# er9x.net
KiCad netlist of a schematic drawn in Altium Designer
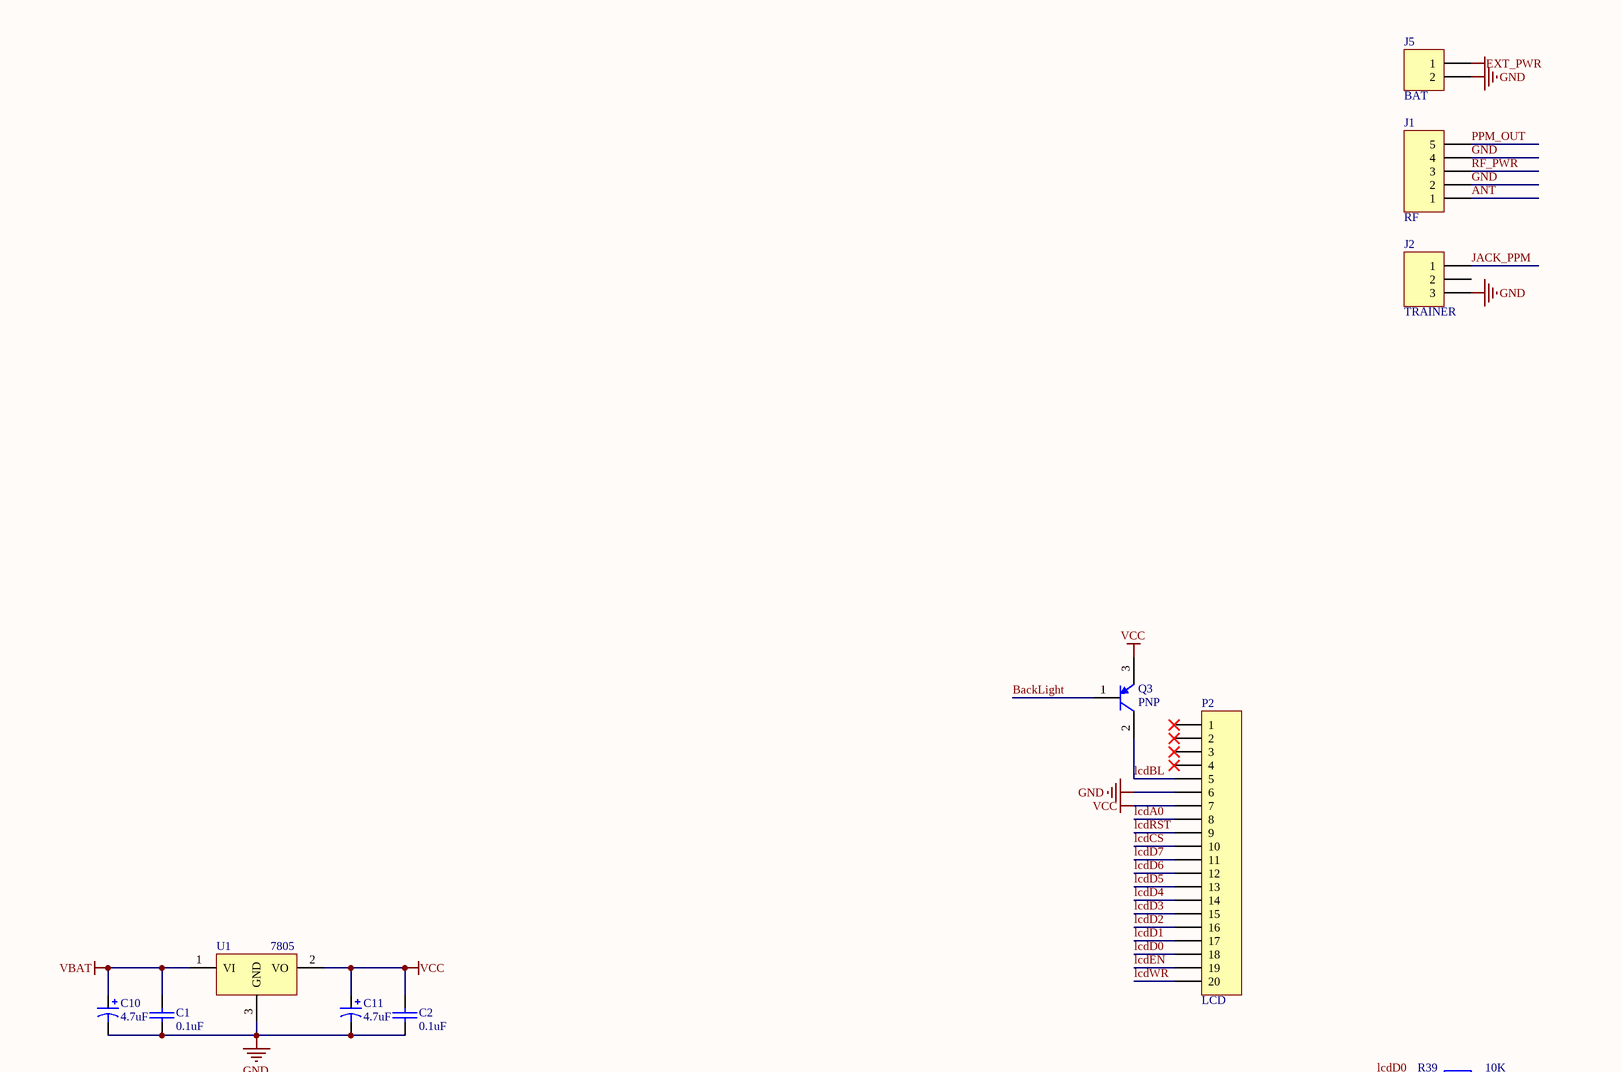
[diagram p0: er9x.SchDoc, top left]
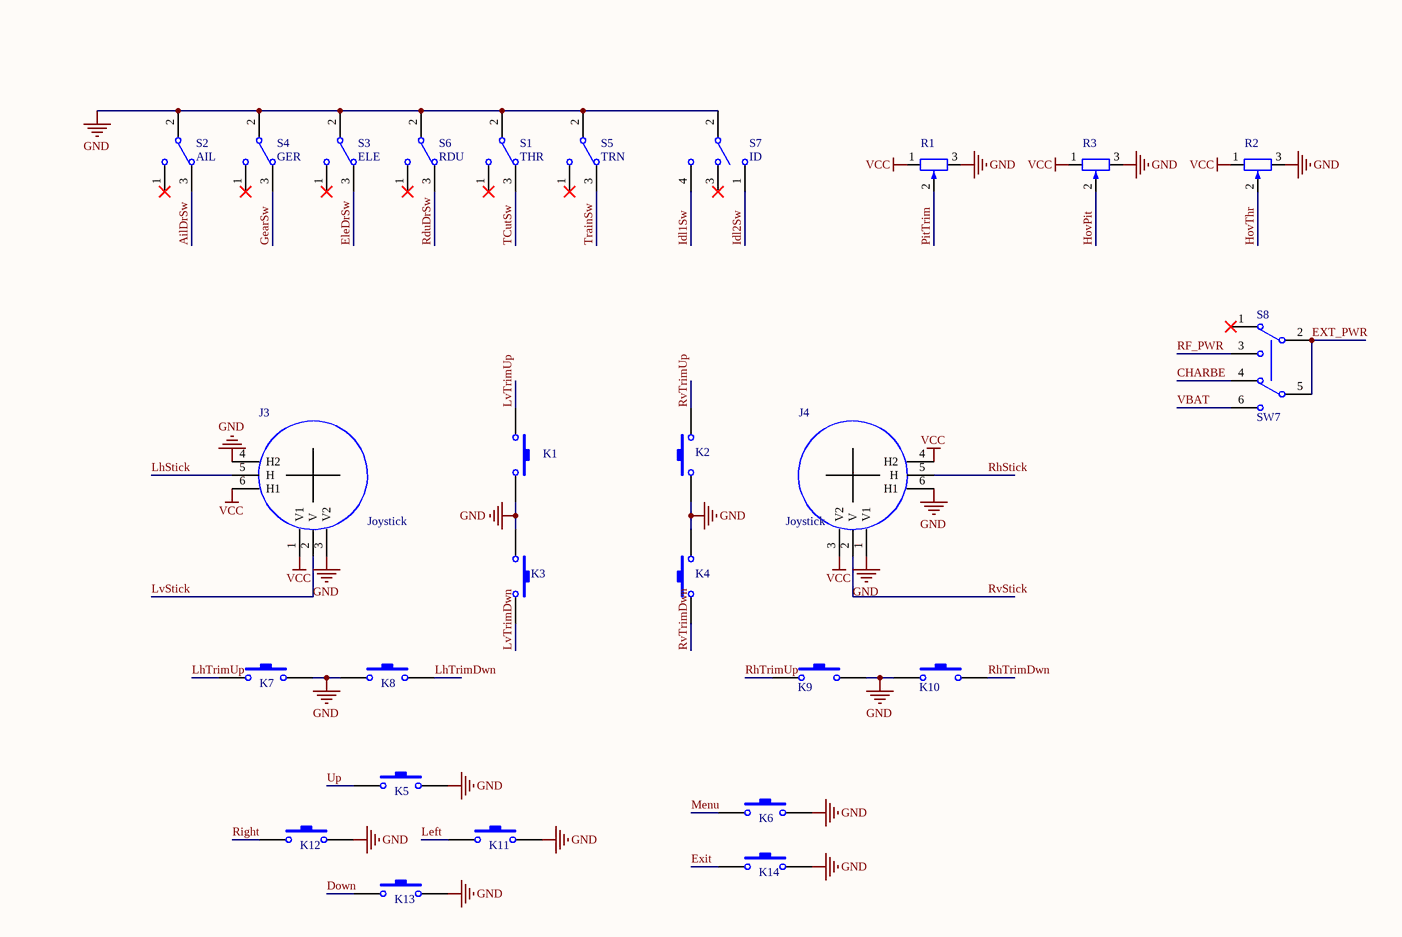
[diagram p1: er9x.SchDoc, top right]
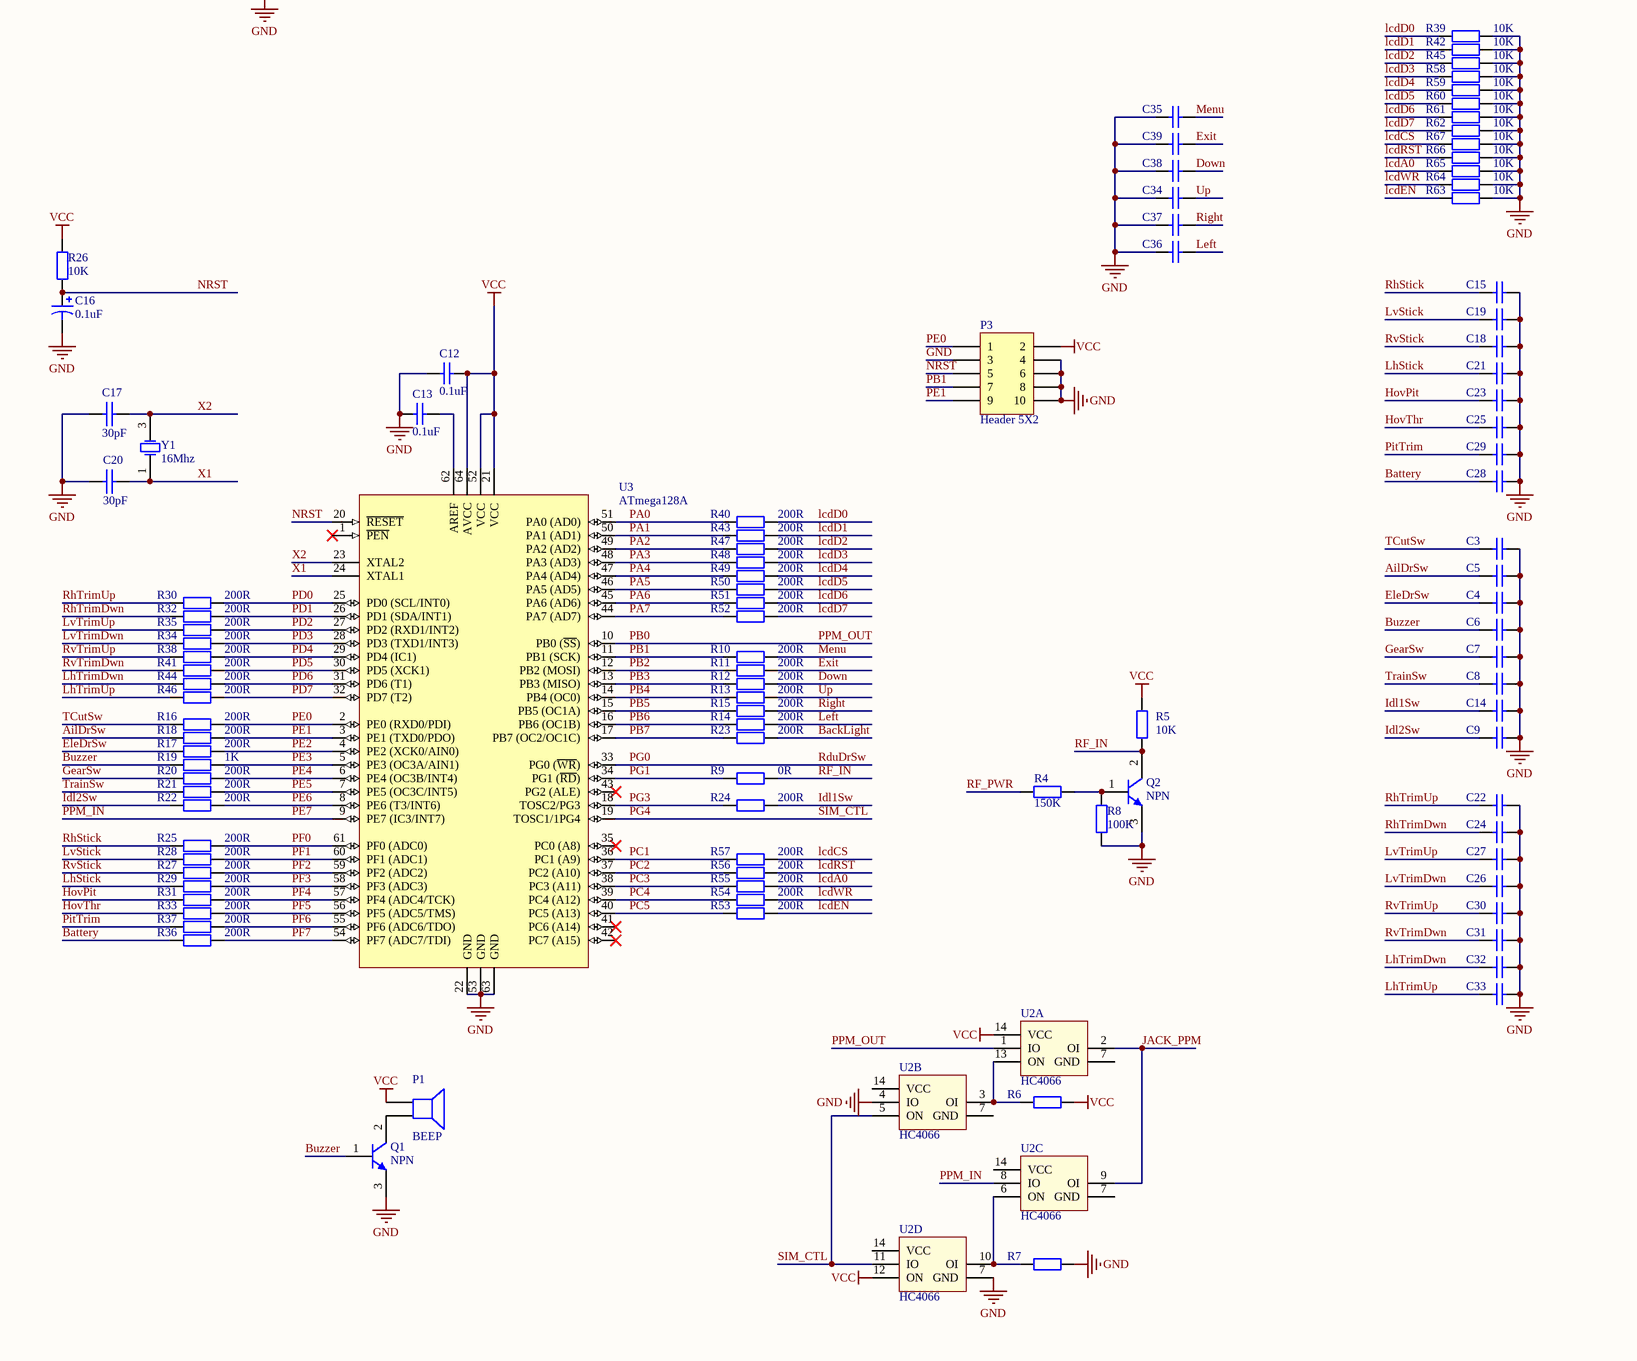
[diagram p2: er9x.SchDoc, bottom left]

(export (version "E")
  (design (tool "Eeschema 10.0.6"))
  (components
    (comp (ref "C1")
      (value "0.1uF")
      (footprint "0603C")
      (description "Capacitor")
      (libsource (lib "*") (part "CAP"))
    )
    (comp (ref "C2")
      (value "0.1uF")
      (footprint "0603C")
      (description "Capacitor")
      (libsource (lib "*") (part "CAP"))
    )
    (comp (ref "C3")
      (value "2.2uF")
      (footprint "0603C")
      (description "Capacitor")
      (fields (field (name "PUBLISHER") "Altium Limited"))
      (libsource (lib "Miscellaneous Devices") (part "Cap"))
    )
    (comp (ref "C4")
      (value "2.2uF")
      (footprint "0603C")
      (description "Capacitor")
      (fields (field (name "PUBLISHER") "Altium Limited"))
      (libsource (lib "Miscellaneous Devices") (part "Cap"))
    )
    (comp (ref "C5")
      (value "2.2uF")
      (footprint "0603C")
      (description "Capacitor")
      (fields (field (name "PUBLISHER") "Altium Limited"))
      (libsource (lib "Miscellaneous Devices") (part "Cap"))
    )
    (comp (ref "C6")
      (value "2.2uF")
      (footprint "0603C")
      (description "Capacitor")
      (fields (field (name "PUBLISHER") "Altium Limited"))
      (libsource (lib "Miscellaneous Devices") (part "Cap"))
    )
    (comp (ref "C7")
      (value "2.2uF")
      (footprint "0603C")
      (description "Capacitor")
      (fields (field (name "PUBLISHER") "Altium Limited"))
      (libsource (lib "Miscellaneous Devices") (part "Cap"))
    )
    (comp (ref "C8")
      (value "2.2uF")
      (footprint "0603C")
      (description "Capacitor")
      (fields (field (name "PUBLISHER") "Altium Limited"))
      (libsource (lib "Miscellaneous Devices") (part "Cap"))
    )
    (comp (ref "C9")
      (value "2.2uF")
      (footprint "0603C")
      (description "Capacitor")
      (fields (field (name "PUBLISHER") "Altium Limited"))
      (libsource (lib "Miscellaneous Devices") (part "Cap"))
    )
    (comp (ref "C10")
      (value "4.7uF")
      (footprint "B")
      (description "Polarized Capacitor (Radial)")
      (fields (field (name "PUBLISHER") "Altium Limited"))
      (libsource (lib "Miscellaneous Devices") (part "Cap Pol1"))
    )
    (comp (ref "C11")
      (value "4.7uF")
      (footprint "B")
      (description "Polarized Capacitor (Radial)")
      (fields (field (name "PUBLISHER") "Altium Limited"))
      (libsource (lib "Miscellaneous Devices") (part "Cap Pol1"))
    )
    (comp (ref "C12")
      (value "0.1uF")
      (footprint "0603C")
      (description "Capacitor")
      (fields (field (name "PUBLISHER") "Altium Limited"))
      (libsource (lib "Miscellaneous Devices") (part "Cap"))
    )
    (comp (ref "C13")
      (value "0.1uF")
      (footprint "0603C")
      (description "Capacitor")
      (fields (field (name "PUBLISHER") "Altium Limited"))
      (libsource (lib "Miscellaneous Devices") (part "Cap"))
    )
    (comp (ref "C14")
      (value "2.2uF")
      (footprint "0603C")
      (description "Capacitor")
      (fields (field (name "PUBLISHER") "Altium Limited"))
      (libsource (lib "Miscellaneous Devices") (part "Cap"))
    )
    (comp (ref "C15")
      (value "2.2uF")
      (footprint "0603C")
      (description "Capacitor")
      (fields (field (name "PUBLISHER") "Altium Limited"))
      (libsource (lib "Miscellaneous Devices") (part "Cap"))
    )
    (comp (ref "C16")
      (value "0.1uF")
      (footprint "0603C")
      (description "Polarized Capacitor (Radial)")
      (fields (field (name "PUBLISHER") "Altium Limited"))
      (libsource (lib "Miscellaneous Devices") (part "Cap Pol1"))
    )
    (comp (ref "C17")
      (value "30pF")
      (footprint "0603C")
      (description "Capacitor")
      (libsource (lib "*") (part "CAP"))
    )
    (comp (ref "C18")
      (value "2.2uF")
      (footprint "0603C")
      (description "Capacitor")
      (fields (field (name "PUBLISHER") "Altium Limited"))
      (libsource (lib "Miscellaneous Devices") (part "Cap"))
    )
    (comp (ref "C19")
      (value "2.2uF")
      (footprint "0603C")
      (description "Capacitor")
      (fields (field (name "PUBLISHER") "Altium Limited"))
      (libsource (lib "Miscellaneous Devices") (part "Cap"))
    )
    (comp (ref "C20")
      (value "30pF")
      (footprint "0603C")
      (description "Capacitor")
      (libsource (lib "*") (part "CAP"))
    )
    (comp (ref "C21")
      (value "2.2uF")
      (footprint "0603C")
      (description "Capacitor")
      (fields (field (name "PUBLISHER") "Altium Limited"))
      (libsource (lib "Miscellaneous Devices") (part "Cap"))
    )
    (comp (ref "C22")
      (value "2.2uF")
      (footprint "0603C")
      (description "Capacitor")
      (fields (field (name "PUBLISHER") "Altium Limited"))
      (libsource (lib "Miscellaneous Devices") (part "Cap"))
    )
    (comp (ref "C23")
      (value "2.2uF")
      (footprint "0603C")
      (description "Capacitor")
      (fields (field (name "PUBLISHER") "Altium Limited"))
      (libsource (lib "Miscellaneous Devices") (part "Cap"))
    )
    (comp (ref "C24")
      (value "2.2uF")
      (footprint "0603C")
      (description "Capacitor")
      (fields (field (name "PUBLISHER") "Altium Limited"))
      (libsource (lib "Miscellaneous Devices") (part "Cap"))
    )
    (comp (ref "C25")
      (value "2.2uF")
      (footprint "0603C")
      (description "Capacitor")
      (fields (field (name "PUBLISHER") "Altium Limited"))
      (libsource (lib "Miscellaneous Devices") (part "Cap"))
    )
    (comp (ref "C26")
      (value "2.2uF")
      (footprint "0603C")
      (description "Capacitor")
      (fields (field (name "PUBLISHER") "Altium Limited"))
      (libsource (lib "Miscellaneous Devices") (part "Cap"))
    )
    (comp (ref "C27")
      (value "2.2uF")
      (footprint "0603C")
      (description "Capacitor")
      (fields (field (name "PUBLISHER") "Altium Limited"))
      (libsource (lib "Miscellaneous Devices") (part "Cap"))
    )
    (comp (ref "C28")
      (value "2.2uF")
      (footprint "0603C")
      (description "Capacitor")
      (fields (field (name "PUBLISHER") "Altium Limited"))
      (libsource (lib "Miscellaneous Devices") (part "Cap"))
    )
    (comp (ref "C29")
      (value "2.2uF")
      (footprint "0603C")
      (description "Capacitor")
      (fields (field (name "PUBLISHER") "Altium Limited"))
      (libsource (lib "Miscellaneous Devices") (part "Cap"))
    )
    (comp (ref "C30")
      (value "2.2uF")
      (footprint "0603C")
      (description "Capacitor")
      (fields (field (name "PUBLISHER") "Altium Limited"))
      (libsource (lib "Miscellaneous Devices") (part "Cap"))
    )
    (comp (ref "C31")
      (value "2.2uF")
      (footprint "0603C")
      (description "Capacitor")
      (fields (field (name "PUBLISHER") "Altium Limited"))
      (libsource (lib "Miscellaneous Devices") (part "Cap"))
    )
    (comp (ref "C32")
      (value "2.2uF")
      (footprint "0603C")
      (description "Capacitor")
      (fields (field (name "PUBLISHER") "Altium Limited"))
      (libsource (lib "Miscellaneous Devices") (part "Cap"))
    )
    (comp (ref "C33")
      (value "2.2uF")
      (footprint "0603C")
      (description "Capacitor")
      (fields (field (name "PUBLISHER") "Altium Limited"))
      (libsource (lib "Miscellaneous Devices") (part "Cap"))
    )
    (comp (ref "C34")
      (value "2.2uF")
      (footprint "0603C")
      (description "Capacitor")
      (fields (field (name "PUBLISHER") "Altium Limited"))
      (libsource (lib "Miscellaneous Devices") (part "Cap"))
    )
    (comp (ref "C35")
      (value "2.2uF")
      (footprint "0603C")
      (description "Capacitor")
      (fields (field (name "PUBLISHER") "Altium Limited"))
      (libsource (lib "Miscellaneous Devices") (part "Cap"))
    )
    (comp (ref "C36")
      (value "2.2uF")
      (footprint "0603C")
      (description "Capacitor")
      (fields (field (name "PUBLISHER") "Altium Limited"))
      (libsource (lib "Miscellaneous Devices") (part "Cap"))
    )
    (comp (ref "C37")
      (value "2.2uF")
      (footprint "0603C")
      (description "Capacitor")
      (fields (field (name "PUBLISHER") "Altium Limited"))
      (libsource (lib "Miscellaneous Devices") (part "Cap"))
    )
    (comp (ref "C38")
      (value "2.2uF")
      (footprint "0603C")
      (description "Capacitor")
      (fields (field (name "PUBLISHER") "Altium Limited"))
      (libsource (lib "Miscellaneous Devices") (part "Cap"))
    )
    (comp (ref "C39")
      (value "2.2uF")
      (footprint "0603C")
      (description "Capacitor")
      (fields (field (name "PUBLISHER") "Altium Limited"))
      (libsource (lib "Miscellaneous Devices") (part "Cap"))
    )
    (comp (ref "J1")
      (value "RF")
      (footprint "HDR1X5")
      (description "Header, 5-Pin")
      (fields (field (name "PUBLISHER") "Altium Limited"))
      (libsource (lib "Miscellaneous Connectors") (part "Header 5"))
    )
    (comp (ref "J2")
      (value "TRAINER")
      (footprint "PJ-393")
      (description "Header, 3-Pin")
      (fields (field (name "PUBLISHER") "Altium Limited"))
      (libsource (lib "Miscellaneous Connectors") (part "Header 3"))
    )
    (comp (ref "J3")
      (value "Joystick")
      (footprint "BIG")
      (description "Square Trimming Potentiometer")
      (fields (field (name "PUBLISHER") "Altium Limited"))
      (libsource (lib "PCB_Project1") (part "RPot SM_1"))
    )
    (comp (ref "J4")
      (value "Joystick")
      (footprint "BIG")
      (description "Square Trimming Potentiometer")
      (fields (field (name "PUBLISHER") "Altium Limited"))
      (libsource (lib "") (part "RPot SM_1_1"))
    )
    (comp (ref "J5")
      (value "BAT")
      (footprint "HDR1X2")
      (description "Header, 2-Pin")
      (fields (field (name "PUBLISHER") "Altium Limited"))
      (libsource (lib "Miscellaneous Connectors") (part "Header 2"))
    )
    (comp (ref "K1")
      (value "SW-PB")
      (footprint "KEY")
      (description "Switch")
      (fields (field (name "PUBLISHER") "Altium Limited"))
      (libsource (lib "Miscellaneous Devices") (part "SW-PB"))
    )
    (comp (ref "K2")
      (value "SW-PB")
      (footprint "KEY")
      (description "Switch")
      (fields (field (name "PUBLISHER") "Altium Limited"))
      (libsource (lib "Miscellaneous Devices") (part "SW-PB"))
    )
    (comp (ref "K3")
      (value "SW-PB")
      (footprint "KEY")
      (description "Switch")
      (fields (field (name "PUBLISHER") "Altium Limited"))
      (libsource (lib "Miscellaneous Devices") (part "SW-PB"))
    )
    (comp (ref "K4")
      (value "SW-PB")
      (footprint "KEY")
      (description "Switch")
      (fields (field (name "PUBLISHER") "Altium Limited"))
      (libsource (lib "Miscellaneous Devices") (part "SW-PB"))
    )
    (comp (ref "K5")
      (value "SW-PB")
      (footprint "KEY")
      (description "Switch")
      (fields (field (name "PUBLISHER") "Altium Limited"))
      (libsource (lib "Miscellaneous Devices") (part "SW-PB"))
    )
    (comp (ref "K6")
      (value "SW-PB")
      (footprint "KEY")
      (description "Switch")
      (fields (field (name "PUBLISHER") "Altium Limited"))
      (libsource (lib "Miscellaneous Devices") (part "SW-PB"))
    )
    (comp (ref "K7")
      (value "SW-PB")
      (footprint "KEY")
      (description "Switch")
      (fields (field (name "PUBLISHER") "Altium Limited"))
      (libsource (lib "Miscellaneous Devices") (part "SW-PB"))
    )
    (comp (ref "K8")
      (value "SW-PB")
      (footprint "KEY")
      (description "Switch")
      (fields (field (name "PUBLISHER") "Altium Limited"))
      (libsource (lib "Miscellaneous Devices") (part "SW-PB"))
    )
    (comp (ref "K9")
      (value "SW-PB")
      (footprint "KEY")
      (description "Switch")
      (fields (field (name "PUBLISHER") "Altium Limited"))
      (libsource (lib "Miscellaneous Devices") (part "SW-PB"))
    )
    (comp (ref "K10")
      (value "SW-PB")
      (footprint "KEY")
      (description "Switch")
      (fields (field (name "PUBLISHER") "Altium Limited"))
      (libsource (lib "Miscellaneous Devices") (part "SW-PB"))
    )
    (comp (ref "K11")
      (value "SW-PB")
      (footprint "KEY")
      (description "Switch")
      (fields (field (name "PUBLISHER") "Altium Limited"))
      (libsource (lib "Miscellaneous Devices") (part "SW-PB"))
    )
    (comp (ref "K12")
      (value "SW-PB")
      (footprint "KEY")
      (description "Switch")
      (fields (field (name "PUBLISHER") "Altium Limited"))
      (libsource (lib "Miscellaneous Devices") (part "SW-PB"))
    )
    (comp (ref "K13")
      (value "SW-PB")
      (footprint "KEY")
      (description "Switch")
      (fields (field (name "PUBLISHER") "Altium Limited"))
      (libsource (lib "Miscellaneous Devices") (part "SW-PB"))
    )
    (comp (ref "K14")
      (value "SW-PB")
      (footprint "KEY")
      (description "Switch")
      (fields (field (name "PUBLISHER") "Altium Limited"))
      (libsource (lib "Miscellaneous Devices") (part "SW-PB"))
    )
    (comp (ref "P1")
      (value "BEEP")
      (footprint "BEEP")
      (description "Loudspeaker")
      (fields (field (name "PUBLISHER") "Altium Limited"))
      (libsource (lib "Miscellaneous Devices") (part "Speaker"))
    )
    (comp (ref "P2")
      (value "LCD")
      (footprint "FPC")
      (description "Header, 20-Pin")
      (fields (field (name "PUBLISHER") "Altium Limited"))
      (libsource (lib "Miscellaneous Connectors") (part "Header 20"))
    )
    (comp (ref "P3")
      (value "Header 5X2")
      (footprint "HDR2X5")
      (description "Header, 5-Pin, Dual row")
      (fields (field (name "PUBLISHER") "Altium Limited"))
      (libsource (lib "Miscellaneous Connectors") (part "Header 5X2"))
    )
    (comp (ref "Q1")
      (value "NPN")
      (footprint "SOT-23")
      (description "NPN Bipolar Transistor")
      (fields (field (name "PUBLISHER") "Altium Limited"))
      (libsource (lib "Miscellaneous Devices") (part "NPN"))
    )
    (comp (ref "Q2")
      (value "NPN")
      (footprint "SOT-23")
      (description "NPN Bipolar Transistor")
      (fields (field (name "PUBLISHER") "Altium Limited"))
      (libsource (lib "Miscellaneous Devices") (part "NPN"))
    )
    (comp (ref "Q3")
      (value "PNP")
      (footprint "SOT-23")
      (description "PNP Bipolar Transistor")
      (fields (field (name "PUBLISHER") "Altium Limited"))
      (libsource (lib "Miscellaneous Devices") (part "PNP"))
    )
    (comp (ref "R1")
      (value "RPot SM")
      (footprint "3296")
      (description "Square Trimming Potentiometer")
      (fields (field (name "PUBLISHER") "Altium Limited"))
      (libsource (lib "PCB_Project1") (part "RPot SM"))
    )
    (comp (ref "R2")
      (value "RPot SM")
      (footprint "3296")
      (description "Square Trimming Potentiometer")
      (fields (field (name "PUBLISHER") "Altium Limited"))
      (libsource (lib "PCB_Project1") (part "RPot SM"))
    )
    (comp (ref "R3")
      (value "RPot SM")
      (footprint "3296")
      (description "Square Trimming Potentiometer")
      (fields (field (name "PUBLISHER") "Altium Limited"))
      (libsource (lib "PCB_Project1") (part "RPot SM"))
    )
    (comp (ref "R4")
      (value "150K")
      (footprint "0603R")
      (description "Resistor")
      (fields (field (name "PUBLISHER") "Altium Limited"))
      (libsource (lib "Miscellaneous Devices") (part "Res2"))
    )
    (comp (ref "R5")
      (value "10K")
      (footprint "0603R")
      (description "Resistor")
      (fields (field (name "PUBLISHER") "Altium Limited"))
      (libsource (lib "") (part "Res2_1"))
    )
    (comp (ref "R6")
      (value "200R")
      (footprint "0603R")
      (description "Resistor")
      (fields (field (name "PUBLISHER") "Altium Limited"))
      (libsource (lib "Miscellaneous Devices") (part "Res2"))
    )
    (comp (ref "R7")
      (value "200R")
      (footprint "0603R")
      (description "Resistor")
      (fields (field (name "PUBLISHER") "Altium Limited"))
      (libsource (lib "Miscellaneous Devices") (part "Res2"))
    )
    (comp (ref "R8")
      (value "100K")
      (footprint "0603R")
      (description "Resistor")
      (fields (field (name "PUBLISHER") "Altium Limited"))
      (libsource (lib "") (part "Res2_2"))
    )
    (comp (ref "R9")
      (value "0R")
      (footprint "0603R")
      (description "Resistor")
      (fields (field (name "PUBLISHER") "Altium Limited"))
      (libsource (lib "Miscellaneous Devices") (part "Res2"))
    )
    (comp (ref "R10")
      (value "200R")
      (footprint "0603R")
      (description "Resistor")
      (fields (field (name "PUBLISHER") "Altium Limited"))
      (libsource (lib "Miscellaneous Devices") (part "Res2"))
    )
    (comp (ref "R11")
      (value "200R")
      (footprint "0603R")
      (description "Resistor")
      (fields (field (name "PUBLISHER") "Altium Limited"))
      (libsource (lib "Miscellaneous Devices") (part "Res2"))
    )
    (comp (ref "R12")
      (value "200R")
      (footprint "0603R")
      (description "Resistor")
      (fields (field (name "PUBLISHER") "Altium Limited"))
      (libsource (lib "Miscellaneous Devices") (part "Res2"))
    )
    (comp (ref "R13")
      (value "200R")
      (footprint "0603R")
      (description "Resistor")
      (fields (field (name "PUBLISHER") "Altium Limited"))
      (libsource (lib "Miscellaneous Devices") (part "Res2"))
    )
    (comp (ref "R14")
      (value "200R")
      (footprint "0603R")
      (description "Resistor")
      (fields (field (name "PUBLISHER") "Altium Limited"))
      (libsource (lib "Miscellaneous Devices") (part "Res2"))
    )
    (comp (ref "R15")
      (value "200R")
      (footprint "0603R")
      (description "Resistor")
      (fields (field (name "PUBLISHER") "Altium Limited"))
      (libsource (lib "Miscellaneous Devices") (part "Res2"))
    )
    (comp (ref "R16")
      (value "200R")
      (footprint "0603R")
      (description "Resistor")
      (fields (field (name "PUBLISHER") "Altium Limited"))
      (libsource (lib "Miscellaneous Devices") (part "Res2"))
    )
    (comp (ref "R17")
      (value "200R")
      (footprint "0603R")
      (description "Resistor")
      (fields (field (name "PUBLISHER") "Altium Limited"))
      (libsource (lib "Miscellaneous Devices") (part "Res2"))
    )
    (comp (ref "R18")
      (value "200R")
      (footprint "0603R")
      (description "Resistor")
      (fields (field (name "PUBLISHER") "Altium Limited"))
      (libsource (lib "Miscellaneous Devices") (part "Res2"))
    )
    (comp (ref "R19")
      (value "1K")
      (footprint "0603R")
      (description "Resistor")
      (fields (field (name "PUBLISHER") "Altium Limited"))
      (libsource (lib "Miscellaneous Devices") (part "Res2"))
    )
    (comp (ref "R20")
      (value "200R")
      (footprint "0603R")
      (description "Resistor")
      (fields (field (name "PUBLISHER") "Altium Limited"))
      (libsource (lib "Miscellaneous Devices") (part "Res2"))
    )
    (comp (ref "R21")
      (value "200R")
      (footprint "0603R")
      (description "Resistor")
      (fields (field (name "PUBLISHER") "Altium Limited"))
      (libsource (lib "Miscellaneous Devices") (part "Res2"))
    )
    (comp (ref "R22")
      (value "200R")
      (footprint "0603R")
      (description "Resistor")
      (fields (field (name "PUBLISHER") "Altium Limited"))
      (libsource (lib "Miscellaneous Devices") (part "Res2"))
    )
    (comp (ref "R23")
      (value "200R")
      (footprint "0603R")
      (description "Resistor")
      (fields (field (name "PUBLISHER") "Altium Limited"))
      (libsource (lib "Miscellaneous Devices") (part "Res2"))
    )
    (comp (ref "R24")
      (value "200R")
      (footprint "0603R")
      (description "Resistor")
      (fields (field (name "PUBLISHER") "Altium Limited"))
      (libsource (lib "Miscellaneous Devices") (part "Res2"))
    )
    (comp (ref "R25")
      (value "200R")
      (footprint "0603R")
      (description "Resistor")
      (fields (field (name "PUBLISHER") "Altium Limited"))
      (libsource (lib "Miscellaneous Devices") (part "Res2"))
    )
    (comp (ref "R26")
      (value "10K")
      (footprint "0603R")
      (description "Resistor")
      (fields (field (name "PUBLISHER") "Altium Limited"))
      (libsource (lib "*") (part "Res2"))
    )
    (comp (ref "R27")
      (value "200R")
      (footprint "0603R")
      (description "Resistor")
      (fields (field (name "PUBLISHER") "Altium Limited"))
      (libsource (lib "Miscellaneous Devices") (part "Res2"))
    )
    (comp (ref "R28")
      (value "200R")
      (footprint "0603R")
      (description "Resistor")
      (fields (field (name "PUBLISHER") "Altium Limited"))
      (libsource (lib "Miscellaneous Devices") (part "Res2"))
    )
    (comp (ref "R29")
      (value "200R")
      (footprint "0603R")
      (description "Resistor")
      (fields (field (name "PUBLISHER") "Altium Limited"))
      (libsource (lib "Miscellaneous Devices") (part "Res2"))
    )
    (comp (ref "R30")
      (value "200R")
      (footprint "0603R")
      (description "Resistor")
      (fields (field (name "PUBLISHER") "Altium Limited"))
      (libsource (lib "Miscellaneous Devices") (part "Res2"))
    )
    (comp (ref "R31")
      (value "200R")
      (footprint "0603R")
      (description "Resistor")
      (fields (field (name "PUBLISHER") "Altium Limited"))
      (libsource (lib "Miscellaneous Devices") (part "Res2"))
    )
    (comp (ref "R32")
      (value "200R")
      (footprint "0603R")
      (description "Resistor")
      (fields (field (name "PUBLISHER") "Altium Limited"))
      (libsource (lib "Miscellaneous Devices") (part "Res2"))
    )
    (comp (ref "R33")
      (value "200R")
      (footprint "0603R")
      (description "Resistor")
      (fields (field (name "PUBLISHER") "Altium Limited"))
      (libsource (lib "Miscellaneous Devices") (part "Res2"))
    )
    (comp (ref "R34")
      (value "200R")
      (footprint "0603R")
      (description "Resistor")
      (fields (field (name "PUBLISHER") "Altium Limited"))
      (libsource (lib "Miscellaneous Devices") (part "Res2"))
    )
    (comp (ref "R35")
      (value "200R")
      (footprint "0603R")
      (description "Resistor")
      (fields (field (name "PUBLISHER") "Altium Limited"))
      (libsource (lib "Miscellaneous Devices") (part "Res2"))
    )
    (comp (ref "R36")
      (value "200R")
      (footprint "0603R")
      (description "Resistor")
      (fields (field (name "PUBLISHER") "Altium Limited"))
      (libsource (lib "Miscellaneous Devices") (part "Res2"))
    )
    (comp (ref "R37")
      (value "200R")
      (footprint "0603R")
      (description "Resistor")
      (fields (field (name "PUBLISHER") "Altium Limited"))
      (libsource (lib "Miscellaneous Devices") (part "Res2"))
    )
    (comp (ref "R38")
      (value "200R")
      (footprint "0603R")
      (description "Resistor")
      (fields (field (name "PUBLISHER") "Altium Limited"))
      (libsource (lib "Miscellaneous Devices") (part "Res2"))
    )
    (comp (ref "R39")
      (value "10K")
      (footprint "0603R")
      (description "Resistor")
      (fields (field (name "PUBLISHER") "Altium Limited"))
      (libsource (lib "Miscellaneous Devices") (part "Res2"))
    )
    (comp (ref "R40")
      (value "200R")
      (footprint "0603R")
      (description "Resistor")
      (fields (field (name "PUBLISHER") "Altium Limited"))
      (libsource (lib "Miscellaneous Devices") (part "Res2"))
    )
    (comp (ref "R41")
      (value "200R")
      (footprint "0603R")
      (description "Resistor")
      (fields (field (name "PUBLISHER") "Altium Limited"))
      (libsource (lib "Miscellaneous Devices") (part "Res2"))
    )
    (comp (ref "R42")
      (value "10K")
      (footprint "0603R")
      (description "Resistor")
      (fields (field (name "PUBLISHER") "Altium Limited"))
      (libsource (lib "Miscellaneous Devices") (part "Res2"))
    )
    (comp (ref "R43")
      (value "200R")
      (footprint "0603R")
      (description "Resistor")
      (fields (field (name "PUBLISHER") "Altium Limited"))
      (libsource (lib "Miscellaneous Devices") (part "Res2"))
    )
    (comp (ref "R44")
      (value "200R")
      (footprint "0603R")
      (description "Resistor")
      (fields (field (name "PUBLISHER") "Altium Limited"))
      (libsource (lib "Miscellaneous Devices") (part "Res2"))
    )
    (comp (ref "R45")
      (value "10K")
      (footprint "0603R")
      (description "Resistor")
      (fields (field (name "PUBLISHER") "Altium Limited"))
      (libsource (lib "Miscellaneous Devices") (part "Res2"))
    )
    (comp (ref "R46")
      (value "200R")
      (footprint "0603R")
      (description "Resistor")
      (fields (field (name "PUBLISHER") "Altium Limited"))
      (libsource (lib "Miscellaneous Devices") (part "Res2"))
    )
    (comp (ref "R47")
      (value "200R")
      (footprint "0603R")
      (description "Resistor")
      (fields (field (name "PUBLISHER") "Altium Limited"))
      (libsource (lib "Miscellaneous Devices") (part "Res2"))
    )
    (comp (ref "R48")
      (value "200R")
      (footprint "0603R")
      (description "Resistor")
      (fields (field (name "PUBLISHER") "Altium Limited"))
      (libsource (lib "Miscellaneous Devices") (part "Res2"))
    )
    (comp (ref "R49")
      (value "200R")
      (footprint "0603R")
      (description "Resistor")
      (fields (field (name "PUBLISHER") "Altium Limited"))
      (libsource (lib "Miscellaneous Devices") (part "Res2"))
    )
    (comp (ref "R50")
      (value "200R")
      (footprint "0603R")
      (description "Resistor")
      (fields (field (name "PUBLISHER") "Altium Limited"))
      (libsource (lib "Miscellaneous Devices") (part "Res2"))
    )
    (comp (ref "R51")
      (value "200R")
      (footprint "0603R")
      (description "Resistor")
      (fields (field (name "PUBLISHER") "Altium Limited"))
      (libsource (lib "Miscellaneous Devices") (part "Res2"))
    )
    (comp (ref "R52")
      (value "200R")
      (footprint "0603R")
      (description "Resistor")
      (fields (field (name "PUBLISHER") "Altium Limited"))
      (libsource (lib "Miscellaneous Devices") (part "Res2"))
    )
    (comp (ref "R53")
      (value "200R")
      (footprint "0603R")
      (description "Resistor")
      (fields (field (name "PUBLISHER") "Altium Limited"))
      (libsource (lib "Miscellaneous Devices") (part "Res2"))
    )
    (comp (ref "R54")
      (value "200R")
      (footprint "0603R")
      (description "Resistor")
      (fields (field (name "PUBLISHER") "Altium Limited"))
      (libsource (lib "Miscellaneous Devices") (part "Res2"))
    )
    (comp (ref "R55")
      (value "200R")
      (footprint "0603R")
      (description "Resistor")
      (fields (field (name "PUBLISHER") "Altium Limited"))
      (libsource (lib "Miscellaneous Devices") (part "Res2"))
    )
    (comp (ref "R56")
      (value "200R")
      (footprint "0603R")
      (description "Resistor")
      (fields (field (name "PUBLISHER") "Altium Limited"))
      (libsource (lib "Miscellaneous Devices") (part "Res2"))
    )
    (comp (ref "R57")
      (value "200R")
      (footprint "0603R")
      (description "Resistor")
      (fields (field (name "PUBLISHER") "Altium Limited"))
      (libsource (lib "Miscellaneous Devices") (part "Res2"))
    )
    (comp (ref "R58")
      (value "10K")
      (footprint "0603R")
      (description "Resistor")
      (fields (field (name "PUBLISHER") "Altium Limited"))
      (libsource (lib "Miscellaneous Devices") (part "Res2"))
    )
    (comp (ref "R59")
      (value "10K")
      (footprint "0603R")
      (description "Resistor")
      (fields (field (name "PUBLISHER") "Altium Limited"))
      (libsource (lib "Miscellaneous Devices") (part "Res2"))
    )
    (comp (ref "R60")
      (value "10K")
      (footprint "0603R")
      (description "Resistor")
      (fields (field (name "PUBLISHER") "Altium Limited"))
      (libsource (lib "Miscellaneous Devices") (part "Res2"))
    )
    (comp (ref "R61")
      (value "10K")
      (footprint "0603R")
      (description "Resistor")
      (fields (field (name "PUBLISHER") "Altium Limited"))
      (libsource (lib "Miscellaneous Devices") (part "Res2"))
    )
    (comp (ref "R62")
      (value "10K")
      (footprint "0603R")
      (description "Resistor")
      (fields (field (name "PUBLISHER") "Altium Limited"))
      (libsource (lib "Miscellaneous Devices") (part "Res2"))
    )
    (comp (ref "R63")
      (value "10K")
      (footprint "0603R")
      (description "Resistor")
      (fields (field (name "PUBLISHER") "Altium Limited"))
      (libsource (lib "Miscellaneous Devices") (part "Res2"))
    )
    (comp (ref "R64")
      (value "10K")
      (footprint "0603R")
      (description "Resistor")
      (fields (field (name "PUBLISHER") "Altium Limited"))
      (libsource (lib "Miscellaneous Devices") (part "Res2"))
    )
    (comp (ref "R65")
      (value "10K")
      (footprint "0603R")
      (description "Resistor")
      (fields (field (name "PUBLISHER") "Altium Limited"))
      (libsource (lib "Miscellaneous Devices") (part "Res2"))
    )
    (comp (ref "R66")
      (value "10K")
      (footprint "0603R")
      (description "Resistor")
      (fields (field (name "PUBLISHER") "Altium Limited"))
      (libsource (lib "Miscellaneous Devices") (part "Res2"))
    )
    (comp (ref "R67")
      (value "10K")
      (footprint "0603R")
      (description "Resistor")
      (fields (field (name "PUBLISHER") "Altium Limited"))
      (libsource (lib "Miscellaneous Devices") (part "Res2"))
    )
    (comp (ref "S1")
      (value "THR")
      (footprint "2235D")
      (description "SPDT Subminiature Toggle Switch, Right Angle Mounting, Vertical Actuation")
      (fields (field (name "PUBLISHER") "Altium Limited"))
      (libsource (lib "Miscellaneous Devices") (part "SW-SPDT"))
    )
    (comp (ref "S2")
      (value "AIL")
      (footprint "2235D")
      (description "SPDT Subminiature Toggle Switch, Right Angle Mounting, Vertical Actuation")
      (fields (field (name "PUBLISHER") "Altium Limited"))
      (libsource (lib "Miscellaneous Devices") (part "SW-SPDT"))
    )
    (comp (ref "S3")
      (value "ELE")
      (footprint "2235D")
      (description "SPDT Subminiature Toggle Switch, Right Angle Mounting, Vertical Actuation")
      (fields (field (name "PUBLISHER") "Altium Limited"))
      (libsource (lib "Miscellaneous Devices") (part "SW-SPDT"))
    )
    (comp (ref "S4")
      (value "GER")
      (footprint "2235D")
      (description "SPDT Subminiature Toggle Switch, Right Angle Mounting, Vertical Actuation")
      (fields (field (name "PUBLISHER") "Altium Limited"))
      (libsource (lib "Miscellaneous Devices") (part "SW-SPDT"))
    )
    (comp (ref "S5")
      (value "TRN")
      (footprint "2235D")
      (description "SPDT Subminiature Toggle Switch, Right Angle Mounting, Vertical Actuation")
      (fields (field (name "PUBLISHER") "Altium Limited"))
      (libsource (lib "Miscellaneous Devices") (part "SW-SPDT"))
    )
    (comp (ref "S6")
      (value "RDU")
      (footprint "2235D")
      (description "SPDT Subminiature Toggle Switch, Right Angle Mounting, Vertical Actuation")
      (fields (field (name "PUBLISHER") "Altium Limited"))
      (libsource (lib "Miscellaneous Devices") (part "SW-SPDT"))
    )
    (comp (ref "S7")
      (value "ID")
      (footprint "2336D")
      (description "Switch")
      (fields (field (name "PUBLISHER") "Altium Limited"))
      (libsource (lib "PCB_Project1") (part "SW DPDT"))
    )
    (comp (ref "S8")
      (value "SW7")
      (footprint "LOCK")
      (description "SPDT Subminiature Toggle Switch, Right Angle Mounting, Vertical Actuation")
      (fields (field (name "PUBLISHER") "Altium Limited"))
      (libsource (lib "PCB_Project1") (part "SW-SPDT"))
    )
    (comp (ref "U1")
      (value "7805")
      (footprint "TO-263")
      (description "Header, 3-Pin, Dual row")
      (fields (field (name "PUBLISHER") "Altium Limited"))
      (libsource (lib "PCB_Project1") (part "7805"))
    )
    (comp (ref "U2")
      (value "HC4066")
      (footprint "TSSOP-14")
      (fields (field (name "PUBLISHER") "Altium Limited"))
      (libsource (lib "PCB_Project1") (part "HC4066"))
    )
    (comp (ref "U3")
      (value "ATmega128A")
      (footprint "LQFP-64")
      (description "8-Bit AVR Microcontroller with 128K Bytes of In-System Programmable Flash Memory")
      (fields (field (name "PUBLISHER") "Altium Limited"))
      (libsource (lib "PCB_Project1") (part "ATmega128L-8MC"))
    )
    (comp (ref "Y1")
      (value "16Mhz")
      (footprint "3225")
      (description "Crystal Oscillator")
      (fields (field (name "PUBLISHER") "Altium Limited"))
      (libsource (lib "CORE") (part "XTAL"))
    )
  )
  (nets
    (net (code "1") (name "/ANT") (class "Default")
      (node (ref "J1") (pin "1") (pinfunction "1_1") (pintype "passive"))
    )
    (net (code "2") (name "/AilDrSw") (class "Default")
      (node (ref "C5") (pin "1") (pinfunction "1_1") (pintype "passive"))
      (node (ref "R18") (pin "2") (pinfunction "2_2") (pintype "passive"))
      (node (ref "S2") (pin "3") (pinfunction "3_3") (pintype "passive"))
    )
    (net (code "3") (name "/BackLight") (class "Default")
      (node (ref "Q3") (pin "1") (pinfunction "B_1") (pintype "passive"))
      (node (ref "R23") (pin "1") (pinfunction "1_1") (pintype "passive"))
    )
    (net (code "4") (name "/Battery") (class "Default")
      (node (ref "C28") (pin "1") (pinfunction "1_1") (pintype "passive"))
      (node (ref "R36") (pin "2") (pinfunction "2_2") (pintype "passive"))
    )
    (net (code "5") (name "/Buzzer") (class "Default")
      (node (ref "C6") (pin "1") (pinfunction "1_1") (pintype "passive"))
      (node (ref "Q1") (pin "1") (pinfunction "B_1") (pintype "passive"))
      (node (ref "R19") (pin "2") (pinfunction "2_2") (pintype "passive"))
    )
    (net (code "6") (name "/CHARBE") (class "Default")
      (node (ref "S8") (pin "4") (pinfunction "3_4") (pintype "passive"))
    )
    (net (code "7") (name "/Down") (class "Default")
      (node (ref "C38") (pin "2") (pinfunction "2_2") (pintype "passive"))
      (node (ref "K13") (pin "1") (pinfunction "1_1") (pintype "passive"))
      (node (ref "R12") (pin "1") (pinfunction "1_1") (pintype "passive"))
    )
    (net (code "8") (name "/EleDrSw") (class "Default")
      (node (ref "C4") (pin "1") (pinfunction "1_1") (pintype "passive"))
      (node (ref "R17") (pin "2") (pinfunction "2_2") (pintype "passive"))
      (node (ref "S3") (pin "3") (pinfunction "3_3") (pintype "passive"))
    )
    (net (code "9") (name "/Exit") (class "Default")
      (node (ref "C39") (pin "2") (pinfunction "2_2") (pintype "passive"))
      (node (ref "K14") (pin "1") (pinfunction "1_1") (pintype "passive"))
      (node (ref "R11") (pin "1") (pinfunction "1_1") (pintype "passive"))
    )
    (net (code "10") (name "/GearSw") (class "Default")
      (node (ref "C7") (pin "1") (pinfunction "1_1") (pintype "passive"))
      (node (ref "R20") (pin "2") (pinfunction "2_2") (pintype "passive"))
      (node (ref "S4") (pin "3") (pinfunction "3_3") (pintype "passive"))
    )
    (net (code "11") (name "/HovPit") (class "Default")
      (node (ref "C23") (pin "1") (pinfunction "1_1") (pintype "passive"))
      (node (ref "R3") (pin "2") (pinfunction "W_2") (pintype "passive"))
      (node (ref "R31") (pin "2") (pinfunction "2_2") (pintype "passive"))
    )
    (net (code "12") (name "/HovThr") (class "Default")
      (node (ref "C25") (pin "1") (pinfunction "1_1") (pintype "passive"))
      (node (ref "R2") (pin "2") (pinfunction "W_2") (pintype "passive"))
      (node (ref "R33") (pin "2") (pinfunction "2_2") (pintype "passive"))
    )
    (net (code "13") (name "/Idl1Sw") (class "Default")
      (node (ref "C14") (pin "1") (pinfunction "1_1") (pintype "passive"))
      (node (ref "R24") (pin "1") (pinfunction "1_1") (pintype "passive"))
      (node (ref "S7") (pin "4") (pinfunction "NC2_4") (pintype "passive"))
    )
    (net (code "14") (name "/Idl2Sw") (class "Default")
      (node (ref "C9") (pin "1") (pinfunction "1_1") (pintype "passive"))
      (node (ref "R22") (pin "2") (pinfunction "2_2") (pintype "passive"))
      (node (ref "S7") (pin "1") (pinfunction "COMMON1_1") (pintype "passive"))
    )
    (net (code "15") (name "/JACK_PPM") (class "Default")
      (node (ref "J2") (pin "1") (pinfunction "1_1") (pintype "passive"))
      (node (ref "U2") (pin "2") (pinfunction "OI_2") (pintype "passive"))
      (node (ref "U2") (pin "9") (pinfunction "OI_9") (pintype "passive"))
    )
    (net (code "16") (name "/Left") (class "Default")
      (node (ref "C36") (pin "2") (pinfunction "2_2") (pintype "passive"))
      (node (ref "K11") (pin "1") (pinfunction "1_1") (pintype "passive"))
      (node (ref "R14") (pin "1") (pinfunction "1_1") (pintype "passive"))
    )
    (net (code "17") (name "/LhStick") (class "Default")
      (node (ref "C21") (pin "1") (pinfunction "1_1") (pintype "passive"))
      (node (ref "J3") (pin "5") (pinfunction "H_5") (pintype "passive"))
      (node (ref "R29") (pin "2") (pinfunction "2_2") (pintype "passive"))
    )
    (net (code "18") (name "/LhTrimDwn") (class "Default")
      (node (ref "C32") (pin "1") (pinfunction "1_1") (pintype "passive"))
      (node (ref "K8") (pin "2") (pinfunction "2_2") (pintype "passive"))
      (node (ref "R44") (pin "2") (pinfunction "2_2") (pintype "passive"))
    )
    (net (code "19") (name "/LhTrimUp") (class "Default")
      (node (ref "C33") (pin "1") (pinfunction "1_1") (pintype "passive"))
      (node (ref "K7") (pin "1") (pinfunction "1_1") (pintype "passive"))
      (node (ref "R46") (pin "2") (pinfunction "2_2") (pintype "passive"))
    )
    (net (code "20") (name "/LvStick") (class "Default")
      (node (ref "C19") (pin "1") (pinfunction "1_1") (pintype "passive"))
      (node (ref "J3") (pin "2") (pinfunction "V_2") (pintype "passive"))
      (node (ref "R28") (pin "2") (pinfunction "2_2") (pintype "passive"))
    )
    (net (code "21") (name "/LvTrimDwn") (class "Default")
      (node (ref "C26") (pin "1") (pinfunction "1_1") (pintype "passive"))
      (node (ref "K3") (pin "2") (pinfunction "2_2") (pintype "passive"))
      (node (ref "R34") (pin "2") (pinfunction "2_2") (pintype "passive"))
    )
    (net (code "22") (name "/LvTrimUp") (class "Default")
      (node (ref "C27") (pin "1") (pinfunction "1_1") (pintype "passive"))
      (node (ref "K1") (pin "1") (pinfunction "1_1") (pintype "passive"))
      (node (ref "R35") (pin "2") (pinfunction "2_2") (pintype "passive"))
    )
    (net (code "23") (name "/Menu") (class "Default")
      (node (ref "C35") (pin "2") (pinfunction "2_2") (pintype "passive"))
      (node (ref "K6") (pin "1") (pinfunction "1_1") (pintype "passive"))
      (node (ref "R10") (pin "1") (pinfunction "1_1") (pintype "passive"))
    )
    (net (code "24") (name "/NRST") (class "Default")
      (node (ref "C16") (pin "1") (pinfunction "1_1") (pintype "passive"))
      (node (ref "P3") (pin "5") (pinfunction "5_5") (pintype "passive"))
      (node (ref "R26") (pin "1") (pinfunction "1_1") (pintype "passive"))
      (node (ref "U3") (pin "20") (pinfunction "~{RESET}_20") (pintype "input"))
    )
    (net (code "25") (name "/PA0") (class "Default")
      (node (ref "R40") (pin "2") (pinfunction "2_2") (pintype "passive"))
      (node (ref "U3") (pin "51") (pinfunction "PA0_(AD0)_51") (pintype "bidirectional"))
    )
    (net (code "26") (name "/PA1") (class "Default")
      (node (ref "R43") (pin "2") (pinfunction "2_2") (pintype "passive"))
      (node (ref "U3") (pin "50") (pinfunction "PA1_(AD1)_50") (pintype "bidirectional"))
    )
    (net (code "27") (name "/PA2") (class "Default")
      (node (ref "R47") (pin "2") (pinfunction "2_2") (pintype "passive"))
      (node (ref "U3") (pin "49") (pinfunction "PA2_(AD2)_49") (pintype "bidirectional"))
    )
    (net (code "28") (name "/PA3") (class "Default")
      (node (ref "R48") (pin "2") (pinfunction "2_2") (pintype "passive"))
      (node (ref "U3") (pin "48") (pinfunction "PA3_(AD3)_48") (pintype "bidirectional"))
    )
    (net (code "29") (name "/PA4") (class "Default")
      (node (ref "R49") (pin "2") (pinfunction "2_2") (pintype "passive"))
      (node (ref "U3") (pin "47") (pinfunction "PA4_(AD4)_47") (pintype "bidirectional"))
    )
    (net (code "30") (name "/PA5") (class "Default")
      (node (ref "R50") (pin "2") (pinfunction "2_2") (pintype "passive"))
      (node (ref "U3") (pin "46") (pinfunction "PA5_(AD5)_46") (pintype "bidirectional"))
    )
    (net (code "31") (name "/PA6") (class "Default")
      (node (ref "R51") (pin "2") (pinfunction "2_2") (pintype "passive"))
      (node (ref "U3") (pin "45") (pinfunction "PA6_(AD6)_45") (pintype "bidirectional"))
    )
    (net (code "32") (name "/PA7") (class "Default")
      (node (ref "R52") (pin "2") (pinfunction "2_2") (pintype "passive"))
      (node (ref "U3") (pin "44") (pinfunction "PA7_(AD7)_44") (pintype "bidirectional"))
    )
    (net (code "33") (name "/PB0") (class "Default")
      (node (ref "J1") (pin "5") (pinfunction "5_5") (pintype "passive"))
      (node (ref "U2") (pin "1") (pinfunction "IO_1") (pintype "passive"))
      (node (ref "U3") (pin "10") (pinfunction "PB0_(~{SS})_10") (pintype "bidirectional"))
    )
    (net (code "34") (name "/PB1") (class "Default")
      (node (ref "P3") (pin "7") (pinfunction "7_7") (pintype "passive"))
      (node (ref "R10") (pin "2") (pinfunction "2_2") (pintype "passive"))
      (node (ref "U3") (pin "11") (pinfunction "PB1_(SCK)_11") (pintype "bidirectional"))
    )
    (net (code "35") (name "/PB2") (class "Default")
      (node (ref "R11") (pin "2") (pinfunction "2_2") (pintype "passive"))
      (node (ref "U3") (pin "12") (pinfunction "PB2_(MOSI)_12") (pintype "bidirectional"))
    )
    (net (code "36") (name "/PB3") (class "Default")
      (node (ref "R12") (pin "2") (pinfunction "2_2") (pintype "passive"))
      (node (ref "U3") (pin "13") (pinfunction "PB3_(MISO)_13") (pintype "bidirectional"))
    )
    (net (code "37") (name "/PB4") (class "Default")
      (node (ref "R13") (pin "2") (pinfunction "2_2") (pintype "passive"))
      (node (ref "U3") (pin "14") (pinfunction "PB4_(OC0)_14") (pintype "bidirectional"))
    )
    (net (code "38") (name "/PB5") (class "Default")
      (node (ref "R15") (pin "2") (pinfunction "2_2") (pintype "passive"))
      (node (ref "U3") (pin "15") (pinfunction "PB5_(OC1A)_15") (pintype "bidirectional"))
    )
    (net (code "39") (name "/PB6") (class "Default")
      (node (ref "R14") (pin "2") (pinfunction "2_2") (pintype "passive"))
      (node (ref "U3") (pin "16") (pinfunction "PB6_(OC1B)_16") (pintype "bidirectional"))
    )
    (net (code "40") (name "/PB7") (class "Default")
      (node (ref "R23") (pin "2") (pinfunction "2_2") (pintype "passive"))
      (node (ref "U3") (pin "17") (pinfunction "PB7_(OC2/OC1C)_17") (pintype "bidirectional"))
    )
    (net (code "41") (name "/PC1") (class "Default")
      (node (ref "R57") (pin "2") (pinfunction "2_2") (pintype "passive"))
      (node (ref "U3") (pin "36") (pinfunction "PC1_(A9)_36") (pintype "bidirectional"))
    )
    (net (code "42") (name "/PC2") (class "Default")
      (node (ref "R56") (pin "2") (pinfunction "2_2") (pintype "passive"))
      (node (ref "U3") (pin "37") (pinfunction "PC2_(A10)_37") (pintype "bidirectional"))
    )
    (net (code "43") (name "/PC3") (class "Default")
      (node (ref "R55") (pin "2") (pinfunction "2_2") (pintype "passive"))
      (node (ref "U3") (pin "38") (pinfunction "PC3_(A11)_38") (pintype "bidirectional"))
    )
    (net (code "44") (name "/PC4") (class "Default")
      (node (ref "R54") (pin "2") (pinfunction "2_2") (pintype "passive"))
      (node (ref "U3") (pin "39") (pinfunction "PC4_(A12)_39") (pintype "bidirectional"))
    )
    (net (code "45") (name "/PC5") (class "Default")
      (node (ref "R53") (pin "2") (pinfunction "2_2") (pintype "passive"))
      (node (ref "U3") (pin "40") (pinfunction "PC5_(A13)_40") (pintype "bidirectional"))
    )
    (net (code "46") (name "/PD0") (class "Default")
      (node (ref "R30") (pin "1") (pinfunction "1_1") (pintype "passive"))
      (node (ref "U3") (pin "25") (pinfunction "PD0_(SCL/INT0)_25") (pintype "bidirectional"))
    )
    (net (code "47") (name "/PD1") (class "Default")
      (node (ref "R32") (pin "1") (pinfunction "1_1") (pintype "passive"))
      (node (ref "U3") (pin "26") (pinfunction "PD1_(SDA/INT1)_26") (pintype "bidirectional"))
    )
    (net (code "48") (name "/PD2") (class "Default")
      (node (ref "R35") (pin "1") (pinfunction "1_1") (pintype "passive"))
      (node (ref "U3") (pin "27") (pinfunction "PD2_(RXD1/INT2)_27") (pintype "bidirectional"))
    )
    (net (code "49") (name "/PD3") (class "Default")
      (node (ref "R34") (pin "1") (pinfunction "1_1") (pintype "passive"))
      (node (ref "U3") (pin "28") (pinfunction "PD3_(TXD1/INT3)_28") (pintype "bidirectional"))
    )
    (net (code "50") (name "/PD4") (class "Default")
      (node (ref "R38") (pin "1") (pinfunction "1_1") (pintype "passive"))
      (node (ref "U3") (pin "29") (pinfunction "PD4_(IC1)_29") (pintype "bidirectional"))
    )
    (net (code "51") (name "/PD5") (class "Default")
      (node (ref "R41") (pin "1") (pinfunction "1_1") (pintype "passive"))
      (node (ref "U3") (pin "30") (pinfunction "PD5_(XCK1)_30") (pintype "bidirectional"))
    )
    (net (code "52") (name "/PD6") (class "Default")
      (node (ref "R44") (pin "1") (pinfunction "1_1") (pintype "passive"))
      (node (ref "U3") (pin "31") (pinfunction "PD6_(T1)_31") (pintype "bidirectional"))
    )
    (net (code "53") (name "/PD7") (class "Default")
      (node (ref "R46") (pin "1") (pinfunction "1_1") (pintype "passive"))
      (node (ref "U3") (pin "32") (pinfunction "PD7_(T2)_32") (pintype "bidirectional"))
    )
    (net (code "54") (name "/PE0") (class "Default")
      (node (ref "P3") (pin "1") (pinfunction "1_1") (pintype "passive"))
      (node (ref "R16") (pin "1") (pinfunction "1_1") (pintype "passive"))
      (node (ref "U3") (pin "2") (pinfunction "PE0_(RXD0/PDI)_2") (pintype "bidirectional"))
    )
    (net (code "55") (name "/PE1") (class "Default")
      (node (ref "P3") (pin "9") (pinfunction "9_9") (pintype "passive"))
      (node (ref "R18") (pin "1") (pinfunction "1_1") (pintype "passive"))
      (node (ref "U3") (pin "3") (pinfunction "PE1_(TXD0/PDO)_3") (pintype "bidirectional"))
    )
    (net (code "56") (name "/PE2") (class "Default")
      (node (ref "R17") (pin "1") (pinfunction "1_1") (pintype "passive"))
      (node (ref "U3") (pin "4") (pinfunction "PE2_(XCK0/AIN0)_4") (pintype "bidirectional"))
    )
    (net (code "57") (name "/PE3") (class "Default")
      (node (ref "R19") (pin "1") (pinfunction "1_1") (pintype "passive"))
      (node (ref "U3") (pin "5") (pinfunction "PE3_(OC3A/AIN1)_5") (pintype "bidirectional"))
    )
    (net (code "58") (name "/PE4") (class "Default")
      (node (ref "R20") (pin "1") (pinfunction "1_1") (pintype "passive"))
      (node (ref "U3") (pin "6") (pinfunction "PE4_(OC3B/INT4)_6") (pintype "bidirectional"))
    )
    (net (code "59") (name "/PE5") (class "Default")
      (node (ref "R21") (pin "1") (pinfunction "1_1") (pintype "passive"))
      (node (ref "U3") (pin "7") (pinfunction "PE5_(OC3C/INT5)_7") (pintype "bidirectional"))
    )
    (net (code "60") (name "/PE6") (class "Default")
      (node (ref "R22") (pin "1") (pinfunction "1_1") (pintype "passive"))
      (node (ref "U3") (pin "8") (pinfunction "PE6_(T3/INT6)_8") (pintype "bidirectional"))
    )
    (net (code "61") (name "/PE7") (class "Default")
      (node (ref "U2") (pin "8") (pinfunction "IO_8") (pintype "passive"))
      (node (ref "U3") (pin "9") (pinfunction "PE7_(IC3/INT7)_9") (pintype "bidirectional"))
    )
    (net (code "62") (name "/PF0") (class "Default")
      (node (ref "R25") (pin "1") (pinfunction "1_1") (pintype "passive"))
      (node (ref "U3") (pin "61") (pinfunction "PF0_(ADC0)_61") (pintype "bidirectional"))
    )
    (net (code "63") (name "/PF1") (class "Default")
      (node (ref "R28") (pin "1") (pinfunction "1_1") (pintype "passive"))
      (node (ref "U3") (pin "60") (pinfunction "PF1_(ADC1)_60") (pintype "bidirectional"))
    )
    (net (code "64") (name "/PF2") (class "Default")
      (node (ref "R27") (pin "1") (pinfunction "1_1") (pintype "passive"))
      (node (ref "U3") (pin "59") (pinfunction "PF2_(ADC2)_59") (pintype "bidirectional"))
    )
    (net (code "65") (name "/PF3") (class "Default")
      (node (ref "R29") (pin "1") (pinfunction "1_1") (pintype "passive"))
      (node (ref "U3") (pin "58") (pinfunction "PF3_(ADC3)_58") (pintype "bidirectional"))
    )
    (net (code "66") (name "/PF4") (class "Default")
      (node (ref "R31") (pin "1") (pinfunction "1_1") (pintype "passive"))
      (node (ref "U3") (pin "57") (pinfunction "PF4_(ADC4/TCK)_57") (pintype "bidirectional"))
    )
    (net (code "67") (name "/PF5") (class "Default")
      (node (ref "R33") (pin "1") (pinfunction "1_1") (pintype "passive"))
      (node (ref "U3") (pin "56") (pinfunction "PF5_(ADC5/TMS)_56") (pintype "bidirectional"))
    )
    (net (code "68") (name "/PF6") (class "Default")
      (node (ref "R37") (pin "1") (pinfunction "1_1") (pintype "passive"))
      (node (ref "U3") (pin "55") (pinfunction "PF6_(ADC6/TDO)_55") (pintype "bidirectional"))
    )
    (net (code "69") (name "/PF7") (class "Default")
      (node (ref "R36") (pin "1") (pinfunction "1_1") (pintype "passive"))
      (node (ref "U3") (pin "54") (pinfunction "PF7_(ADC7/TDI)_54") (pintype "bidirectional"))
    )
    (net (code "70") (name "/PG0") (class "Default")
      (node (ref "S6") (pin "3") (pinfunction "3_3") (pintype "passive"))
      (node (ref "U3") (pin "33") (pinfunction "PG0_(~{WR})_33") (pintype "bidirectional"))
    )
    (net (code "71") (name "/PG1") (class "Default")
      (node (ref "R9") (pin "2") (pinfunction "2_2") (pintype "passive"))
      (node (ref "U3") (pin "34") (pinfunction "PG1_(~{RD})_34") (pintype "bidirectional"))
    )
    (net (code "72") (name "/PG3") (class "Default")
      (node (ref "R24") (pin "2") (pinfunction "2_2") (pintype "passive"))
      (node (ref "U3") (pin "18") (pinfunction "TOSC2/PG3_18") (pintype "bidirectional"))
    )
    (net (code "73") (name "/PG4") (class "Default")
      (node (ref "U2") (pin "11") (pinfunction "IO_11") (pintype "passive"))
      (node (ref "U2") (pin "5") (pinfunction "ON_5") (pintype "passive"))
      (node (ref "U3") (pin "19") (pinfunction "TOSC1/1PG4_19") (pintype "bidirectional"))
    )
    (net (code "74") (name "/PitTrim") (class "Default")
      (node (ref "C29") (pin "1") (pinfunction "1_1") (pintype "passive"))
      (node (ref "R1") (pin "2") (pinfunction "W_2") (pintype "passive"))
      (node (ref "R37") (pin "2") (pinfunction "2_2") (pintype "passive"))
    )
    (net (code "75") (name "/RF_IN") (class "Default")
      (node (ref "Q2") (pin "2") (pinfunction "C_2") (pintype "passive"))
      (node (ref "R5") (pin "2") (pinfunction "2_2") (pintype "passive"))
      (node (ref "R9") (pin "1") (pinfunction "1_1") (pintype "passive"))
    )
    (net (code "76") (name "/RF_PWR") (class "Default")
      (node (ref "J1") (pin "3") (pinfunction "3_3") (pintype "passive"))
      (node (ref "R4") (pin "2") (pinfunction "2_2") (pintype "passive"))
      (node (ref "S8") (pin "3") (pinfunction "1_3") (pintype "passive"))
    )
    (net (code "77") (name "/RhStick") (class "Default")
      (node (ref "C15") (pin "1") (pinfunction "1_1") (pintype "passive"))
      (node (ref "J4") (pin "5") (pinfunction "H_5") (pintype "passive"))
      (node (ref "R25") (pin "2") (pinfunction "2_2") (pintype "passive"))
    )
    (net (code "78") (name "/RhTrimDwn") (class "Default")
      (node (ref "C24") (pin "1") (pinfunction "1_1") (pintype "passive"))
      (node (ref "K10") (pin "1") (pinfunction "1_1") (pintype "passive"))
      (node (ref "R32") (pin "2") (pinfunction "2_2") (pintype "passive"))
    )
    (net (code "79") (name "/RhTrimUp") (class "Default")
      (node (ref "C22") (pin "1") (pinfunction "1_1") (pintype "passive"))
      (node (ref "K9") (pin "2") (pinfunction "2_2") (pintype "passive"))
      (node (ref "R30") (pin "2") (pinfunction "2_2") (pintype "passive"))
    )
    (net (code "80") (name "/Right") (class "Default")
      (node (ref "C37") (pin "2") (pinfunction "2_2") (pintype "passive"))
      (node (ref "K12") (pin "1") (pinfunction "1_1") (pintype "passive"))
      (node (ref "R15") (pin "1") (pinfunction "1_1") (pintype "passive"))
    )
    (net (code "81") (name "/RvStick") (class "Default")
      (node (ref "C18") (pin "1") (pinfunction "1_1") (pintype "passive"))
      (node (ref "J4") (pin "2") (pinfunction "V_2") (pintype "passive"))
      (node (ref "R27") (pin "2") (pinfunction "2_2") (pintype "passive"))
    )
    (net (code "82") (name "/RvTrimDwn") (class "Default")
      (node (ref "C31") (pin "1") (pinfunction "1_1") (pintype "passive"))
      (node (ref "K4") (pin "2") (pinfunction "2_2") (pintype "passive"))
      (node (ref "R41") (pin "2") (pinfunction "2_2") (pintype "passive"))
    )
    (net (code "83") (name "/RvTrimUp") (class "Default")
      (node (ref "C30") (pin "1") (pinfunction "1_1") (pintype "passive"))
      (node (ref "K2") (pin "1") (pinfunction "1_1") (pintype "passive"))
      (node (ref "R38") (pin "2") (pinfunction "2_2") (pintype "passive"))
    )
    (net (code "84") (name "/TCutSw") (class "Default")
      (node (ref "C3") (pin "1") (pinfunction "1_1") (pintype "passive"))
      (node (ref "R16") (pin "2") (pinfunction "2_2") (pintype "passive"))
      (node (ref "S1") (pin "3") (pinfunction "3_3") (pintype "passive"))
    )
    (net (code "85") (name "/TrainSw") (class "Default")
      (node (ref "C8") (pin "1") (pinfunction "1_1") (pintype "passive"))
      (node (ref "R21") (pin "2") (pinfunction "2_2") (pintype "passive"))
      (node (ref "S5") (pin "3") (pinfunction "3_3") (pintype "passive"))
    )
    (net (code "86") (name "/Up") (class "Default")
      (node (ref "C34") (pin "2") (pinfunction "2_2") (pintype "passive"))
      (node (ref "K5") (pin "1") (pinfunction "1_1") (pintype "passive"))
      (node (ref "R13") (pin "1") (pinfunction "1_1") (pintype "passive"))
    )
    (net (code "87") (name "/X1") (class "Default")
      (node (ref "C20") (pin "1") (pinfunction "1_1") (pintype "passive"))
      (node (ref "U3") (pin "24") (pinfunction "XTAL1_24") (pintype "passive"))
      (node (ref "Y1") (pin "1") (pinfunction "OSC1_1") (pintype "passive"))
    )
    (net (code "88") (name "/X2") (class "Default")
      (node (ref "C17") (pin "2") (pinfunction "2_2") (pintype "passive"))
      (node (ref "U3") (pin "23") (pinfunction "XTAL2_23") (pintype "passive"))
      (node (ref "Y1") (pin "3") (pinfunction "OSC2_3") (pintype "passive"))
    )
    (net (code "89") (name "/lcdA0") (class "Default")
      (node (ref "P2") (pin "8") (pinfunction "8_8") (pintype "passive"))
      (node (ref "R55") (pin "1") (pinfunction "1_1") (pintype "passive"))
      (node (ref "R65") (pin "2") (pinfunction "2_2") (pintype "passive"))
    )
    (net (code "90") (name "/lcdBL") (class "Default")
      (node (ref "P2") (pin "5") (pinfunction "5_5") (pintype "passive"))
      (node (ref "Q3") (pin "2") (pinfunction "C_2") (pintype "passive"))
    )
    (net (code "91") (name "/lcdCS") (class "Default")
      (node (ref "P2") (pin "10") (pinfunction "10_10") (pintype "passive"))
      (node (ref "R57") (pin "1") (pinfunction "1_1") (pintype "passive"))
      (node (ref "R67") (pin "2") (pinfunction "2_2") (pintype "passive"))
    )
    (net (code "92") (name "/lcdD0") (class "Default")
      (node (ref "P2") (pin "18") (pinfunction "18_18") (pintype "passive"))
      (node (ref "R39") (pin "2") (pinfunction "2_2") (pintype "passive"))
      (node (ref "R40") (pin "1") (pinfunction "1_1") (pintype "passive"))
    )
    (net (code "93") (name "/lcdD1") (class "Default")
      (node (ref "P2") (pin "17") (pinfunction "17_17") (pintype "passive"))
      (node (ref "R42") (pin "2") (pinfunction "2_2") (pintype "passive"))
      (node (ref "R43") (pin "1") (pinfunction "1_1") (pintype "passive"))
    )
    (net (code "94") (name "/lcdD2") (class "Default")
      (node (ref "P2") (pin "16") (pinfunction "16_16") (pintype "passive"))
      (node (ref "R45") (pin "2") (pinfunction "2_2") (pintype "passive"))
      (node (ref "R47") (pin "1") (pinfunction "1_1") (pintype "passive"))
    )
    (net (code "95") (name "/lcdD3") (class "Default")
      (node (ref "P2") (pin "15") (pinfunction "15_15") (pintype "passive"))
      (node (ref "R48") (pin "1") (pinfunction "1_1") (pintype "passive"))
      (node (ref "R58") (pin "2") (pinfunction "2_2") (pintype "passive"))
    )
    (net (code "96") (name "/lcdD4") (class "Default")
      (node (ref "P2") (pin "14") (pinfunction "14_14") (pintype "passive"))
      (node (ref "R49") (pin "1") (pinfunction "1_1") (pintype "passive"))
      (node (ref "R59") (pin "2") (pinfunction "2_2") (pintype "passive"))
    )
    (net (code "97") (name "/lcdD5") (class "Default")
      (node (ref "P2") (pin "13") (pinfunction "13_13") (pintype "passive"))
      (node (ref "R50") (pin "1") (pinfunction "1_1") (pintype "passive"))
      (node (ref "R60") (pin "2") (pinfunction "2_2") (pintype "passive"))
    )
    (net (code "98") (name "/lcdD6") (class "Default")
      (node (ref "P2") (pin "12") (pinfunction "12_12") (pintype "passive"))
      (node (ref "R51") (pin "1") (pinfunction "1_1") (pintype "passive"))
      (node (ref "R61") (pin "2") (pinfunction "2_2") (pintype "passive"))
    )
    (net (code "99") (name "/lcdD7") (class "Default")
      (node (ref "P2") (pin "11") (pinfunction "11_11") (pintype "passive"))
      (node (ref "R52") (pin "1") (pinfunction "1_1") (pintype "passive"))
      (node (ref "R62") (pin "2") (pinfunction "2_2") (pintype "passive"))
    )
    (net (code "100") (name "/lcdEN") (class "Default")
      (node (ref "P2") (pin "19") (pinfunction "19_19") (pintype "passive"))
      (node (ref "R53") (pin "1") (pinfunction "1_1") (pintype "passive"))
      (node (ref "R63") (pin "2") (pinfunction "2_2") (pintype "passive"))
    )
    (net (code "101") (name "/lcdRST") (class "Default")
      (node (ref "P2") (pin "9") (pinfunction "9_9") (pintype "passive"))
      (node (ref "R56") (pin "1") (pinfunction "1_1") (pintype "passive"))
      (node (ref "R66") (pin "2") (pinfunction "2_2") (pintype "passive"))
    )
    (net (code "102") (name "/lcdWR") (class "Default")
      (node (ref "P2") (pin "20") (pinfunction "20_20") (pintype "passive"))
      (node (ref "R54") (pin "1") (pinfunction "1_1") (pintype "passive"))
      (node (ref "R64") (pin "2") (pinfunction "2_2") (pintype "passive"))
    )
    (net (code "103") (name "EXT_PWR") (class "Default")
      (node (ref "J5") (pin "1") (pinfunction "1_1") (pintype "passive"))
      (node (ref "S8") (pin "2") (pinfunction "2_2") (pintype "passive"))
      (node (ref "S8") (pin "5") (pinfunction "2_5") (pintype "passive"))
    )
    (net (code "104") (name "GND") (class "Default")
      (node (ref "C1") (pin "2") (pinfunction "2_2") (pintype "passive"))
      (node (ref "C10") (pin "2") (pinfunction "2_2") (pintype "passive"))
      (node (ref "C11") (pin "2") (pinfunction "2_2") (pintype "passive"))
      (node (ref "C12") (pin "2") (pinfunction "2_2") (pintype "passive"))
      (node (ref "C13") (pin "2") (pinfunction "2_2") (pintype "passive"))
      (node (ref "C14") (pin "2") (pinfunction "2_2") (pintype "passive"))
      (node (ref "C15") (pin "2") (pinfunction "2_2") (pintype "passive"))
      (node (ref "C16") (pin "2") (pinfunction "2_2") (pintype "passive"))
      (node (ref "C17") (pin "1") (pinfunction "1_1") (pintype "passive"))
      (node (ref "C18") (pin "2") (pinfunction "2_2") (pintype "passive"))
      (node (ref "C19") (pin "2") (pinfunction "2_2") (pintype "passive"))
      (node (ref "C2") (pin "2") (pinfunction "2_2") (pintype "passive"))
      (node (ref "C20") (pin "2") (pinfunction "2_2") (pintype "passive"))
      (node (ref "C21") (pin "2") (pinfunction "2_2") (pintype "passive"))
      (node (ref "C22") (pin "2") (pinfunction "2_2") (pintype "passive"))
      (node (ref "C23") (pin "2") (pinfunction "2_2") (pintype "passive"))
      (node (ref "C24") (pin "2") (pinfunction "2_2") (pintype "passive"))
      (node (ref "C25") (pin "2") (pinfunction "2_2") (pintype "passive"))
      (node (ref "C26") (pin "2") (pinfunction "2_2") (pintype "passive"))
      (node (ref "C27") (pin "2") (pinfunction "2_2") (pintype "passive"))
      (node (ref "C28") (pin "2") (pinfunction "2_2") (pintype "passive"))
      (node (ref "C29") (pin "2") (pinfunction "2_2") (pintype "passive"))
      (node (ref "C3") (pin "2") (pinfunction "2_2") (pintype "passive"))
      (node (ref "C30") (pin "2") (pinfunction "2_2") (pintype "passive"))
      (node (ref "C31") (pin "2") (pinfunction "2_2") (pintype "passive"))
      (node (ref "C32") (pin "2") (pinfunction "2_2") (pintype "passive"))
      (node (ref "C33") (pin "2") (pinfunction "2_2") (pintype "passive"))
      (node (ref "C34") (pin "1") (pinfunction "1_1") (pintype "passive"))
      (node (ref "C35") (pin "1") (pinfunction "1_1") (pintype "passive"))
      (node (ref "C36") (pin "1") (pinfunction "1_1") (pintype "passive"))
      (node (ref "C37") (pin "1") (pinfunction "1_1") (pintype "passive"))
      (node (ref "C38") (pin "1") (pinfunction "1_1") (pintype "passive"))
      (node (ref "C39") (pin "1") (pinfunction "1_1") (pintype "passive"))
      (node (ref "C4") (pin "2") (pinfunction "2_2") (pintype "passive"))
      (node (ref "C5") (pin "2") (pinfunction "2_2") (pintype "passive"))
      (node (ref "C6") (pin "2") (pinfunction "2_2") (pintype "passive"))
      (node (ref "C7") (pin "2") (pinfunction "2_2") (pintype "passive"))
      (node (ref "C8") (pin "2") (pinfunction "2_2") (pintype "passive"))
      (node (ref "C9") (pin "2") (pinfunction "2_2") (pintype "passive"))
      (node (ref "J1") (pin "2") (pinfunction "2_2") (pintype "passive"))
      (node (ref "J1") (pin "4") (pinfunction "4_4") (pintype "passive"))
      (node (ref "J2") (pin "3") (pinfunction "3_3") (pintype "passive"))
      (node (ref "J3") (pin "3") (pinfunction "V2_3") (pintype "passive"))
      (node (ref "J3") (pin "4") (pinfunction "H2_4") (pintype "passive"))
      (node (ref "J4") (pin "1") (pinfunction "V1_1") (pintype "passive"))
      (node (ref "J4") (pin "6") (pinfunction "H1_6") (pintype "passive"))
      (node (ref "J5") (pin "2") (pinfunction "2_2") (pintype "passive"))
      (node (ref "K1") (pin "2") (pinfunction "2_2") (pintype "passive"))
      (node (ref "K10") (pin "2") (pinfunction "2_2") (pintype "passive"))
      (node (ref "K11") (pin "2") (pinfunction "2_2") (pintype "passive"))
      (node (ref "K12") (pin "2") (pinfunction "2_2") (pintype "passive"))
      (node (ref "K13") (pin "2") (pinfunction "2_2") (pintype "passive"))
      (node (ref "K14") (pin "2") (pinfunction "2_2") (pintype "passive"))
      (node (ref "K2") (pin "2") (pinfunction "2_2") (pintype "passive"))
      (node (ref "K3") (pin "1") (pinfunction "1_1") (pintype "passive"))
      (node (ref "K4") (pin "1") (pinfunction "1_1") (pintype "passive"))
      (node (ref "K5") (pin "2") (pinfunction "2_2") (pintype "passive"))
      (node (ref "K6") (pin "2") (pinfunction "2_2") (pintype "passive"))
      (node (ref "K7") (pin "2") (pinfunction "2_2") (pintype "passive"))
      (node (ref "K8") (pin "1") (pinfunction "1_1") (pintype "passive"))
      (node (ref "K9") (pin "1") (pinfunction "1_1") (pintype "passive"))
      (node (ref "P2") (pin "6") (pinfunction "6_6") (pintype "passive"))
      (node (ref "P3") (pin "10") (pinfunction "10_10") (pintype "passive"))
      (node (ref "P3") (pin "3") (pinfunction "3_3") (pintype "passive"))
      (node (ref "P3") (pin "4") (pinfunction "4_4") (pintype "passive"))
      (node (ref "P3") (pin "6") (pinfunction "6_6") (pintype "passive"))
      (node (ref "P3") (pin "8") (pinfunction "8_8") (pintype "passive"))
      (node (ref "Q1") (pin "3") (pinfunction "E_3") (pintype "passive"))
      (node (ref "Q2") (pin "3") (pinfunction "E_3") (pintype "passive"))
      (node (ref "R1") (pin "3") (pinfunction "+_3") (pintype "passive"))
      (node (ref "R2") (pin "3") (pinfunction "+_3") (pintype "passive"))
      (node (ref "R3") (pin "3") (pinfunction "+_3") (pintype "passive"))
      (node (ref "R39") (pin "1") (pinfunction "1_1") (pintype "passive"))
      (node (ref "R42") (pin "1") (pinfunction "1_1") (pintype "passive"))
      (node (ref "R45") (pin "1") (pinfunction "1_1") (pintype "passive"))
      (node (ref "R58") (pin "1") (pinfunction "1_1") (pintype "passive"))
      (node (ref "R59") (pin "1") (pinfunction "1_1") (pintype "passive"))
      (node (ref "R60") (pin "1") (pinfunction "1_1") (pintype "passive"))
      (node (ref "R61") (pin "1") (pinfunction "1_1") (pintype "passive"))
      (node (ref "R62") (pin "1") (pinfunction "1_1") (pintype "passive"))
      (node (ref "R63") (pin "1") (pinfunction "1_1") (pintype "passive"))
      (node (ref "R64") (pin "1") (pinfunction "1_1") (pintype "passive"))
      (node (ref "R65") (pin "1") (pinfunction "1_1") (pintype "passive"))
      (node (ref "R66") (pin "1") (pinfunction "1_1") (pintype "passive"))
      (node (ref "R67") (pin "1") (pinfunction "1_1") (pintype "passive"))
      (node (ref "R7") (pin "1") (pinfunction "1_1") (pintype "passive"))
      (node (ref "R8") (pin "1") (pinfunction "1_1") (pintype "passive"))
      (node (ref "S1") (pin "2") (pinfunction "2_2") (pintype "passive"))
      (node (ref "S2") (pin "2") (pinfunction "2_2") (pintype "passive"))
      (node (ref "S3") (pin "2") (pinfunction "2_2") (pintype "passive"))
      (node (ref "S4") (pin "2") (pinfunction "2_2") (pintype "passive"))
      (node (ref "S5") (pin "2") (pinfunction "2_2") (pintype "passive"))
      (node (ref "S6") (pin "2") (pinfunction "2_2") (pintype "passive"))
      (node (ref "S7") (pin "2") (pinfunction "NC1_2") (pintype "passive"))
      (node (ref "U1") (pin "3") (pinfunction "GND_3") (pintype "passive"))
      (node (ref "U2") (pin "4") (pinfunction "IO_4") (pintype "passive"))
      (node (ref "U2") (pin "7") (pinfunction "GND_7") (pintype "passive"))
      (node (ref "U3") (pin "22") (pinfunction "GND_22") (pintype "power_in"))
      (node (ref "U3") (pin "53") (pinfunction "GND_53") (pintype "power_in"))
      (node (ref "U3") (pin "63") (pinfunction "GND_63") (pintype "power_in"))
    )
    (net (code "105") (name "Net-(Q1-C)") (class "Default")
      (node (ref "P1") (pin "2") (pinfunction "2_2") (pintype "passive"))
      (node (ref "Q1") (pin "2") (pinfunction "C_2") (pintype "passive"))
    )
    (net (code "106") (name "Net-(Q2-B)") (class "Default")
      (node (ref "Q2") (pin "1") (pinfunction "B_1") (pintype "passive"))
      (node (ref "R4") (pin "1") (pinfunction "1_1") (pintype "passive"))
      (node (ref "R8") (pin "2") (pinfunction "2_2") (pintype "passive"))
    )
    (net (code "107") (name "Net-(U2A-ON)") (class "Default")
      (node (ref "R6") (pin "2") (pinfunction "2_2") (pintype "passive"))
      (node (ref "U2") (pin "13") (pinfunction "ON_13") (pintype "passive"))
      (node (ref "U2") (pin "3") (pinfunction "OI_3") (pintype "passive"))
    )
    (net (code "108") (name "Net-(U2C-ON)") (class "Default")
      (node (ref "R7") (pin "2") (pinfunction "2_2") (pintype "passive"))
      (node (ref "U2") (pin "10") (pinfunction "OI_10") (pintype "passive"))
      (node (ref "U2") (pin "6") (pinfunction "ON_6") (pintype "passive"))
    )
    (net (code "109") (name "Net-(U3-AREF)") (class "Default")
      (node (ref "C13") (pin "1") (pinfunction "1_1") (pintype "passive"))
      (node (ref "U3") (pin "62") (pinfunction "AREF_62") (pintype "passive"))
    )
    (net (code "110") (name "VBAT") (class "Default")
      (node (ref "C1") (pin "1") (pinfunction "1_1") (pintype "passive"))
      (node (ref "C10") (pin "1") (pinfunction "1_1") (pintype "passive"))
      (node (ref "S8") (pin "6") (pinfunction "1_6") (pintype "passive"))
      (node (ref "U1") (pin "1") (pinfunction "VI_1") (pintype "passive"))
    )
    (net (code "111") (name "VCC") (class "Default")
      (node (ref "C11") (pin "1") (pinfunction "1_1") (pintype "passive"))
      (node (ref "C12") (pin "1") (pinfunction "1_1") (pintype "passive"))
      (node (ref "C2") (pin "1") (pinfunction "1_1") (pintype "passive"))
      (node (ref "J3") (pin "1") (pinfunction "V1_1") (pintype "passive"))
      (node (ref "J3") (pin "6") (pinfunction "H1_6") (pintype "passive"))
      (node (ref "J4") (pin "3") (pinfunction "V2_3") (pintype "passive"))
      (node (ref "J4") (pin "4") (pinfunction "H2_4") (pintype "passive"))
      (node (ref "P1") (pin "1") (pinfunction "1_1") (pintype "passive"))
      (node (ref "P2") (pin "7") (pinfunction "7_7") (pintype "passive"))
      (node (ref "P3") (pin "2") (pinfunction "2_2") (pintype "passive"))
      (node (ref "Q3") (pin "3") (pinfunction "E_3") (pintype "passive"))
      (node (ref "R1") (pin "1") (pinfunction "-_1") (pintype "passive"))
      (node (ref "R2") (pin "1") (pinfunction "-_1") (pintype "passive"))
      (node (ref "R26") (pin "2") (pinfunction "2_2") (pintype "passive"))
      (node (ref "R3") (pin "1") (pinfunction "-_1") (pintype "passive"))
      (node (ref "R5") (pin "1") (pinfunction "1_1") (pintype "passive"))
      (node (ref "R6") (pin "1") (pinfunction "1_1") (pintype "passive"))
      (node (ref "U1") (pin "2") (pinfunction "VO_2") (pintype "passive"))
      (node (ref "U2") (pin "12") (pinfunction "ON_12") (pintype "passive"))
      (node (ref "U2") (pin "14") (pinfunction "VCC_14") (pintype "passive"))
      (node (ref "U3") (pin "21") (pinfunction "VCC_21") (pintype "power_in"))
      (node (ref "U3") (pin "52") (pinfunction "VCC_52") (pintype "power_in"))
      (node (ref "U3") (pin "64") (pinfunction "AVCC_64") (pintype "power_in"))
    )
    (net (code "112") (name "unconnected-(J2-Pad2)") (class "Default")
      (node (ref "J2") (pin "2") (pinfunction "2_2") (pintype "passive"))
    )
    (net (code "113") (name "unconnected-(P2-Pad1)") (class "Default")
      (node (ref "P2") (pin "1") (pinfunction "1_1") (pintype "passive+no_connect"))
    )
    (net (code "114") (name "unconnected-(P2-Pad2)") (class "Default")
      (node (ref "P2") (pin "2") (pinfunction "2_2") (pintype "passive+no_connect"))
    )
    (net (code "115") (name "unconnected-(P2-Pad3)") (class "Default")
      (node (ref "P2") (pin "3") (pinfunction "3_3") (pintype "passive+no_connect"))
    )
    (net (code "116") (name "unconnected-(P2-Pad4)") (class "Default")
      (node (ref "P2") (pin "4") (pinfunction "4_4") (pintype "passive+no_connect"))
    )
    (net (code "117") (name "unconnected-(S1-Pad1)") (class "Default")
      (node (ref "S1") (pin "1") (pinfunction "1_1") (pintype "passive+no_connect"))
    )
    (net (code "118") (name "unconnected-(S2-Pad1)") (class "Default")
      (node (ref "S2") (pin "1") (pinfunction "1_1") (pintype "passive+no_connect"))
    )
    (net (code "119") (name "unconnected-(S3-Pad1)") (class "Default")
      (node (ref "S3") (pin "1") (pinfunction "1_1") (pintype "passive+no_connect"))
    )
    (net (code "120") (name "unconnected-(S4-Pad1)") (class "Default")
      (node (ref "S4") (pin "1") (pinfunction "1_1") (pintype "passive+no_connect"))
    )
    (net (code "121") (name "unconnected-(S5-Pad1)") (class "Default")
      (node (ref "S5") (pin "1") (pinfunction "1_1") (pintype "passive+no_connect"))
    )
    (net (code "122") (name "unconnected-(S6-Pad1)") (class "Default")
      (node (ref "S6") (pin "1") (pinfunction "1_1") (pintype "passive+no_connect"))
    )
    (net (code "123") (name "unconnected-(S7-NO1-Pad3)") (class "Default")
      (node (ref "S7") (pin "3") (pinfunction "NO1_3") (pintype "passive+no_connect"))
    )
    (net (code "124") (name "unconnected-(S8-3-Pad1)") (class "Default")
      (node (ref "S8") (pin "1") (pinfunction "3_1") (pintype "passive+no_connect"))
    )
    (net (code "125") (name "unconnected-(U2A-GND-Pad7)") (class "Default")
      (node (ref "U2") (pin "7") (pinfunction "GND_7") (pintype "passive"))
    )
    (net (code "126") (name "unconnected-(U2B-GND-Pad7)") (class "Default")
      (node (ref "U2") (pin "7") (pinfunction "GND_7") (pintype "passive"))
    )
    (net (code "127") (name "unconnected-(U2B-VCC-Pad14)") (class "Default")
      (node (ref "U2") (pin "14") (pinfunction "VCC_14") (pintype "passive"))
    )
    (net (code "128") (name "unconnected-(U2C-GND-Pad7)") (class "Default")
      (node (ref "U2") (pin "7") (pinfunction "GND_7") (pintype "passive"))
    )
    (net (code "129") (name "unconnected-(U2C-VCC-Pad14)") (class "Default")
      (node (ref "U2") (pin "14") (pinfunction "VCC_14") (pintype "passive"))
    )
    (net (code "130") (name "unconnected-(U2D-VCC-Pad14)") (class "Default")
      (node (ref "U2") (pin "14") (pinfunction "VCC_14") (pintype "passive"))
    )
    (net (code "131") (name "unconnected-(U3-PC0_(A8)-Pad35)") (class "Default")
      (node (ref "U3") (pin "35") (pinfunction "PC0_(A8)_35") (pintype "bidirectional+no_connect"))
    )
    (net (code "132") (name "unconnected-(U3-PC6_(A14)-Pad41)") (class "Default")
      (node (ref "U3") (pin "41") (pinfunction "PC6_(A14)_41") (pintype "bidirectional+no_connect"))
    )
    (net (code "133") (name "unconnected-(U3-PC7_(A15)-Pad42)") (class "Default")
      (node (ref "U3") (pin "42") (pinfunction "PC7_(A15)_42") (pintype "bidirectional+no_connect"))
    )
    (net (code "134") (name "unconnected-(U3-PG2_(ALE)-Pad43)") (class "Default")
      (node (ref "U3") (pin "43") (pinfunction "PG2_(ALE)_43") (pintype "bidirectional+no_connect"))
    )
    (net (code "135") (name "unconnected-(U3-~{PEN}-Pad1)") (class "Default")
      (node (ref "U3") (pin "1") (pinfunction "~{PEN}_1") (pintype "input+no_connect"))
    )
  )
)
